# db9-can-hub01.net
KiCad netlist of a schematic drawn in EAGLE
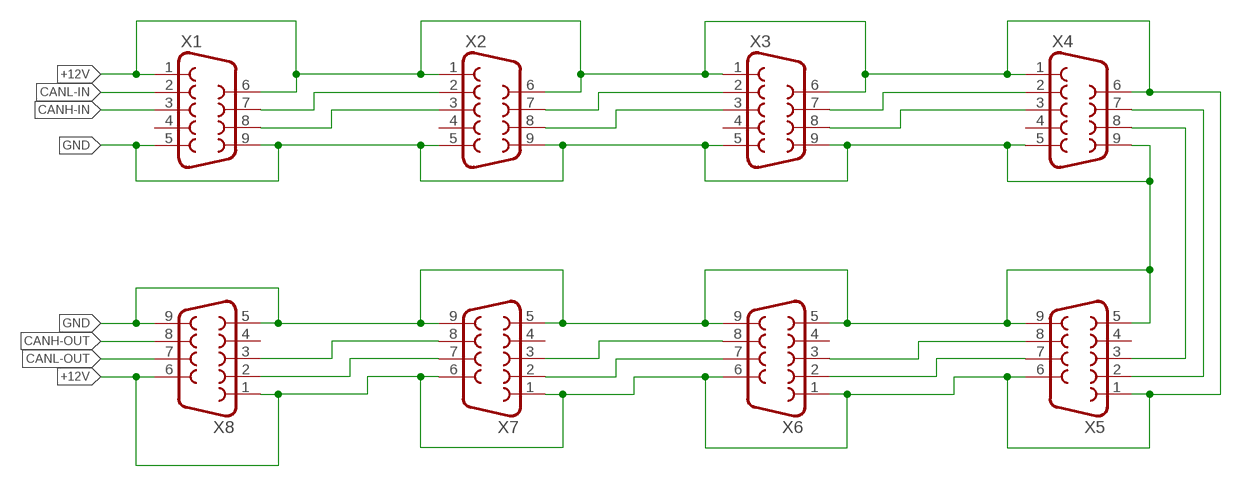
[diagram p0: schematic, sheet 1]

(export (version "E")
  (design (tool "Eeschema 10.0.6"))
  (components
    (comp (ref "X1")
      (value "F09H")
      (footprint "eagle-import:F09H")
      (libsource (lib "eagle-import") (part "F09H"))
    )
    (comp (ref "X2")
      (value "F09H")
      (footprint "eagle-import:F09H")
      (libsource (lib "eagle-import") (part "F09H"))
    )
    (comp (ref "X3")
      (value "F09H")
      (footprint "eagle-import:F09H")
      (libsource (lib "eagle-import") (part "F09H"))
    )
    (comp (ref "X4")
      (value "F09H")
      (footprint "eagle-import:F09H")
      (libsource (lib "eagle-import") (part "F09H"))
    )
    (comp (ref "X5")
      (value "F09H")
      (footprint "eagle-import:F09H")
      (libsource (lib "eagle-import") (part "F09H"))
    )
    (comp (ref "X6")
      (value "F09H")
      (footprint "eagle-import:F09H")
      (libsource (lib "eagle-import") (part "F09H"))
    )
    (comp (ref "X7")
      (value "F09H")
      (footprint "eagle-import:F09H")
      (libsource (lib "eagle-import") (part "F09H"))
    )
    (comp (ref "X8")
      (value "F09H")
      (footprint "eagle-import:F09H")
      (libsource (lib "eagle-import") (part "F09H"))
    )
  )
  (nets
    (net (code "1") (name "+12V") (class "Default")
      (node (ref "X1") (pin "1") (pinfunction "1_1") (pintype "passive"))
      (node (ref "X1") (pin "6") (pinfunction "6_6") (pintype "passive"))
      (node (ref "X2") (pin "1") (pinfunction "1_1") (pintype "passive"))
      (node (ref "X2") (pin "6") (pinfunction "6_6") (pintype "passive"))
      (node (ref "X3") (pin "1") (pinfunction "1_1") (pintype "passive"))
      (node (ref "X3") (pin "6") (pinfunction "6_6") (pintype "passive"))
      (node (ref "X4") (pin "1") (pinfunction "1_1") (pintype "passive"))
      (node (ref "X4") (pin "6") (pinfunction "6_6") (pintype "passive"))
      (node (ref "X5") (pin "1") (pinfunction "1_1") (pintype "passive"))
      (node (ref "X5") (pin "6") (pinfunction "6_6") (pintype "passive"))
      (node (ref "X6") (pin "1") (pinfunction "1_1") (pintype "passive"))
      (node (ref "X6") (pin "6") (pinfunction "6_6") (pintype "passive"))
      (node (ref "X7") (pin "1") (pinfunction "1_1") (pintype "passive"))
      (node (ref "X7") (pin "6") (pinfunction "6_6") (pintype "passive"))
      (node (ref "X8") (pin "1") (pinfunction "1_1") (pintype "passive"))
      (node (ref "X8") (pin "6") (pinfunction "6_6") (pintype "passive"))
    )
    (net (code "2") (name "CANH-IN") (class "Default")
      (node (ref "X1") (pin "3") (pinfunction "3_3") (pintype "passive"))
    )
    (net (code "3") (name "CANH-OUT") (class "Default")
      (node (ref "X8") (pin "8") (pinfunction "8_8") (pintype "passive"))
    )
    (net (code "4") (name "CANL-IN") (class "Default")
      (node (ref "X1") (pin "2") (pinfunction "2_2") (pintype "passive"))
    )
    (net (code "5") (name "CANL-OUT") (class "Default")
      (node (ref "X8") (pin "7") (pinfunction "7_7") (pintype "passive"))
    )
    (net (code "6") (name "GND") (class "Default")
      (node (ref "X1") (pin "5") (pinfunction "5_5") (pintype "passive"))
      (node (ref "X1") (pin "9") (pinfunction "9_9") (pintype "passive"))
      (node (ref "X2") (pin "5") (pinfunction "5_5") (pintype "passive"))
      (node (ref "X2") (pin "9") (pinfunction "9_9") (pintype "passive"))
      (node (ref "X3") (pin "5") (pinfunction "5_5") (pintype "passive"))
      (node (ref "X3") (pin "9") (pinfunction "9_9") (pintype "passive"))
      (node (ref "X4") (pin "5") (pinfunction "5_5") (pintype "passive"))
      (node (ref "X4") (pin "9") (pinfunction "9_9") (pintype "passive"))
      (node (ref "X5") (pin "5") (pinfunction "5_5") (pintype "passive"))
      (node (ref "X5") (pin "9") (pinfunction "9_9") (pintype "passive"))
      (node (ref "X6") (pin "5") (pinfunction "5_5") (pintype "passive"))
      (node (ref "X6") (pin "9") (pinfunction "9_9") (pintype "passive"))
      (node (ref "X7") (pin "5") (pinfunction "5_5") (pintype "passive"))
      (node (ref "X7") (pin "9") (pinfunction "9_9") (pintype "passive"))
      (node (ref "X8") (pin "5") (pinfunction "5_5") (pintype "passive"))
      (node (ref "X8") (pin "9") (pinfunction "9_9") (pintype "passive"))
    )
    (net (code "7") (name "Net-(X1-Pad7)") (class "Default")
      (node (ref "X1") (pin "7") (pinfunction "7_7") (pintype "passive"))
      (node (ref "X2") (pin "2") (pinfunction "2_2") (pintype "passive"))
    )
    (net (code "8") (name "Net-(X1-Pad8)") (class "Default")
      (node (ref "X1") (pin "8") (pinfunction "8_8") (pintype "passive"))
      (node (ref "X2") (pin "3") (pinfunction "3_3") (pintype "passive"))
    )
    (net (code "9") (name "Net-(X2-Pad7)") (class "Default")
      (node (ref "X2") (pin "7") (pinfunction "7_7") (pintype "passive"))
      (node (ref "X3") (pin "2") (pinfunction "2_2") (pintype "passive"))
    )
    (net (code "10") (name "Net-(X2-Pad8)") (class "Default")
      (node (ref "X2") (pin "8") (pinfunction "8_8") (pintype "passive"))
      (node (ref "X3") (pin "3") (pinfunction "3_3") (pintype "passive"))
    )
    (net (code "11") (name "Net-(X3-Pad7)") (class "Default")
      (node (ref "X3") (pin "7") (pinfunction "7_7") (pintype "passive"))
      (node (ref "X4") (pin "2") (pinfunction "2_2") (pintype "passive"))
    )
    (net (code "12") (name "Net-(X3-Pad8)") (class "Default")
      (node (ref "X3") (pin "8") (pinfunction "8_8") (pintype "passive"))
      (node (ref "X4") (pin "3") (pinfunction "3_3") (pintype "passive"))
    )
    (net (code "13") (name "Net-(X4-Pad7)") (class "Default")
      (node (ref "X4") (pin "7") (pinfunction "7_7") (pintype "passive"))
      (node (ref "X5") (pin "2") (pinfunction "2_2") (pintype "passive"))
    )
    (net (code "14") (name "Net-(X4-Pad8)") (class "Default")
      (node (ref "X4") (pin "8") (pinfunction "8_8") (pintype "passive"))
      (node (ref "X5") (pin "3") (pinfunction "3_3") (pintype "passive"))
    )
    (net (code "15") (name "Net-(X5-Pad7)") (class "Default")
      (node (ref "X5") (pin "7") (pinfunction "7_7") (pintype "passive"))
      (node (ref "X6") (pin "2") (pinfunction "2_2") (pintype "passive"))
    )
    (net (code "16") (name "Net-(X5-Pad8)") (class "Default")
      (node (ref "X5") (pin "8") (pinfunction "8_8") (pintype "passive"))
      (node (ref "X6") (pin "3") (pinfunction "3_3") (pintype "passive"))
    )
    (net (code "17") (name "Net-(X6-Pad7)") (class "Default")
      (node (ref "X6") (pin "7") (pinfunction "7_7") (pintype "passive"))
      (node (ref "X7") (pin "2") (pinfunction "2_2") (pintype "passive"))
    )
    (net (code "18") (name "Net-(X6-Pad8)") (class "Default")
      (node (ref "X6") (pin "8") (pinfunction "8_8") (pintype "passive"))
      (node (ref "X7") (pin "3") (pinfunction "3_3") (pintype "passive"))
    )
    (net (code "19") (name "Net-(X7-Pad7)") (class "Default")
      (node (ref "X7") (pin "7") (pinfunction "7_7") (pintype "passive"))
      (node (ref "X8") (pin "2") (pinfunction "2_2") (pintype "passive"))
    )
    (net (code "20") (name "Net-(X7-Pad8)") (class "Default")
      (node (ref "X7") (pin "8") (pinfunction "8_8") (pintype "passive"))
      (node (ref "X8") (pin "3") (pinfunction "3_3") (pintype "passive"))
    )
    (net (code "21") (name "unconnected-(X1-Pad4)") (class "Default")
      (node (ref "X1") (pin "4") (pinfunction "4_4") (pintype "passive"))
    )
    (net (code "22") (name "unconnected-(X2-Pad4)") (class "Default")
      (node (ref "X2") (pin "4") (pinfunction "4_4") (pintype "passive"))
    )
    (net (code "23") (name "unconnected-(X3-Pad4)") (class "Default")
      (node (ref "X3") (pin "4") (pinfunction "4_4") (pintype "passive"))
    )
    (net (code "24") (name "unconnected-(X4-Pad4)") (class "Default")
      (node (ref "X4") (pin "4") (pinfunction "4_4") (pintype "passive"))
    )
    (net (code "25") (name "unconnected-(X5-Pad4)") (class "Default")
      (node (ref "X5") (pin "4") (pinfunction "4_4") (pintype "passive"))
    )
    (net (code "26") (name "unconnected-(X6-Pad4)") (class "Default")
      (node (ref "X6") (pin "4") (pinfunction "4_4") (pintype "passive"))
    )
    (net (code "27") (name "unconnected-(X7-Pad4)") (class "Default")
      (node (ref "X7") (pin "4") (pinfunction "4_4") (pintype "passive"))
    )
    (net (code "28") (name "unconnected-(X8-Pad4)") (class "Default")
      (node (ref "X8") (pin "4") (pinfunction "4_4") (pintype "passive"))
    )
  )
)
